# New_Multirotor_CPU_imu_V1_3.net
KiCad netlist of a schematic drawn in EAGLE
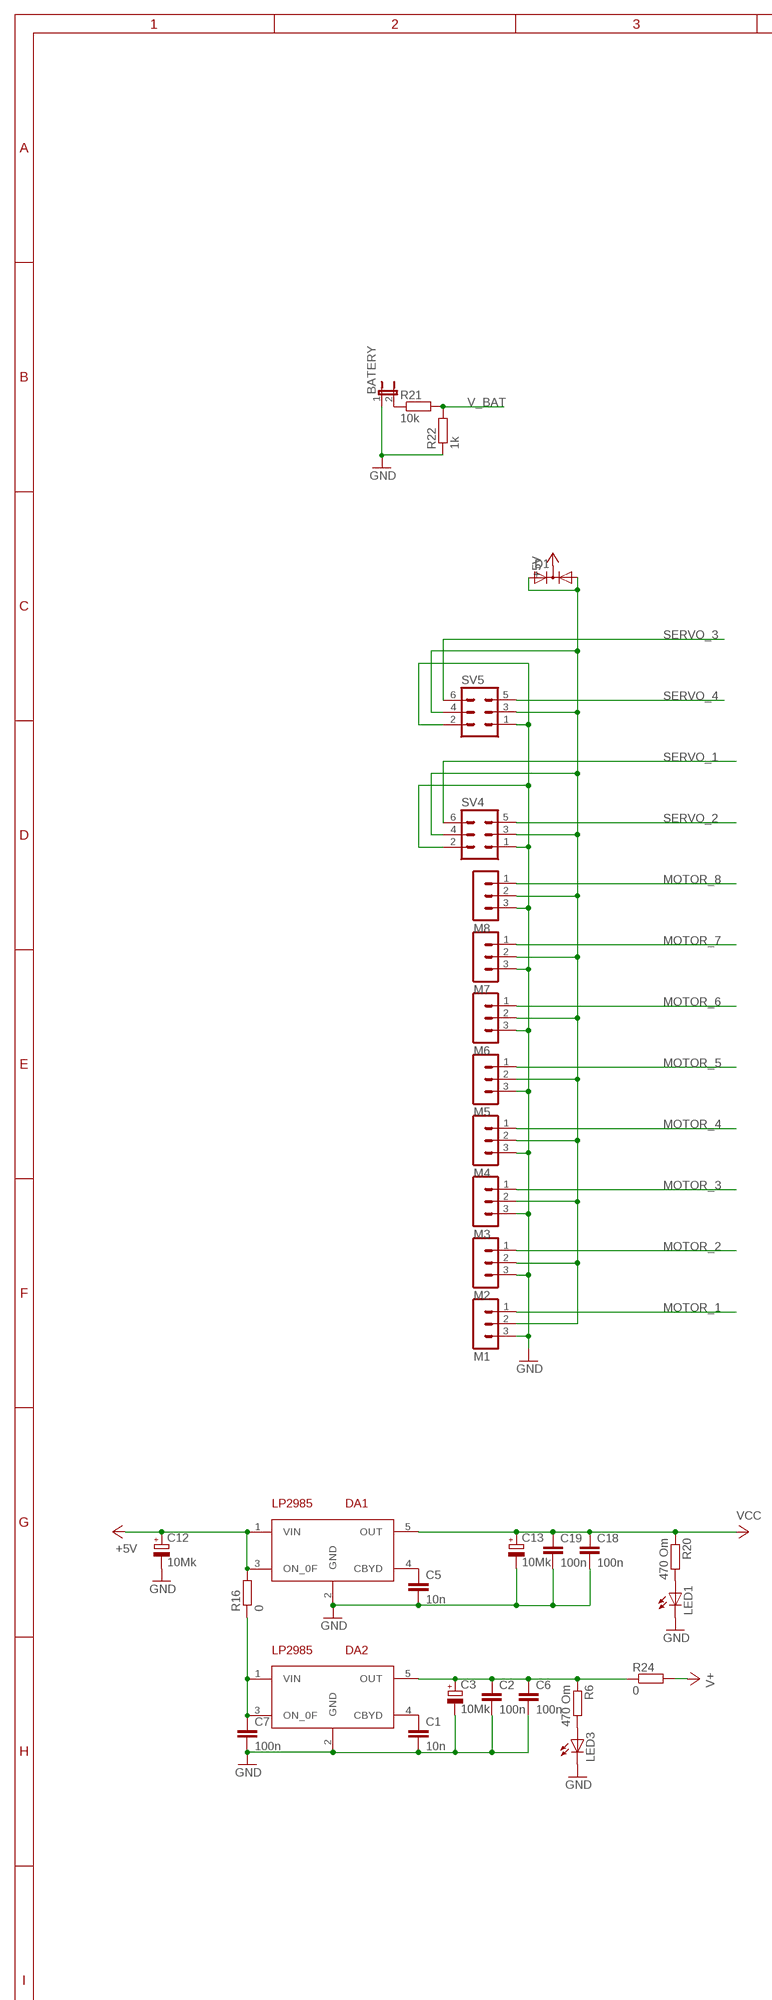
[diagram p0: schematic, sheet 1, part 1 of 2]
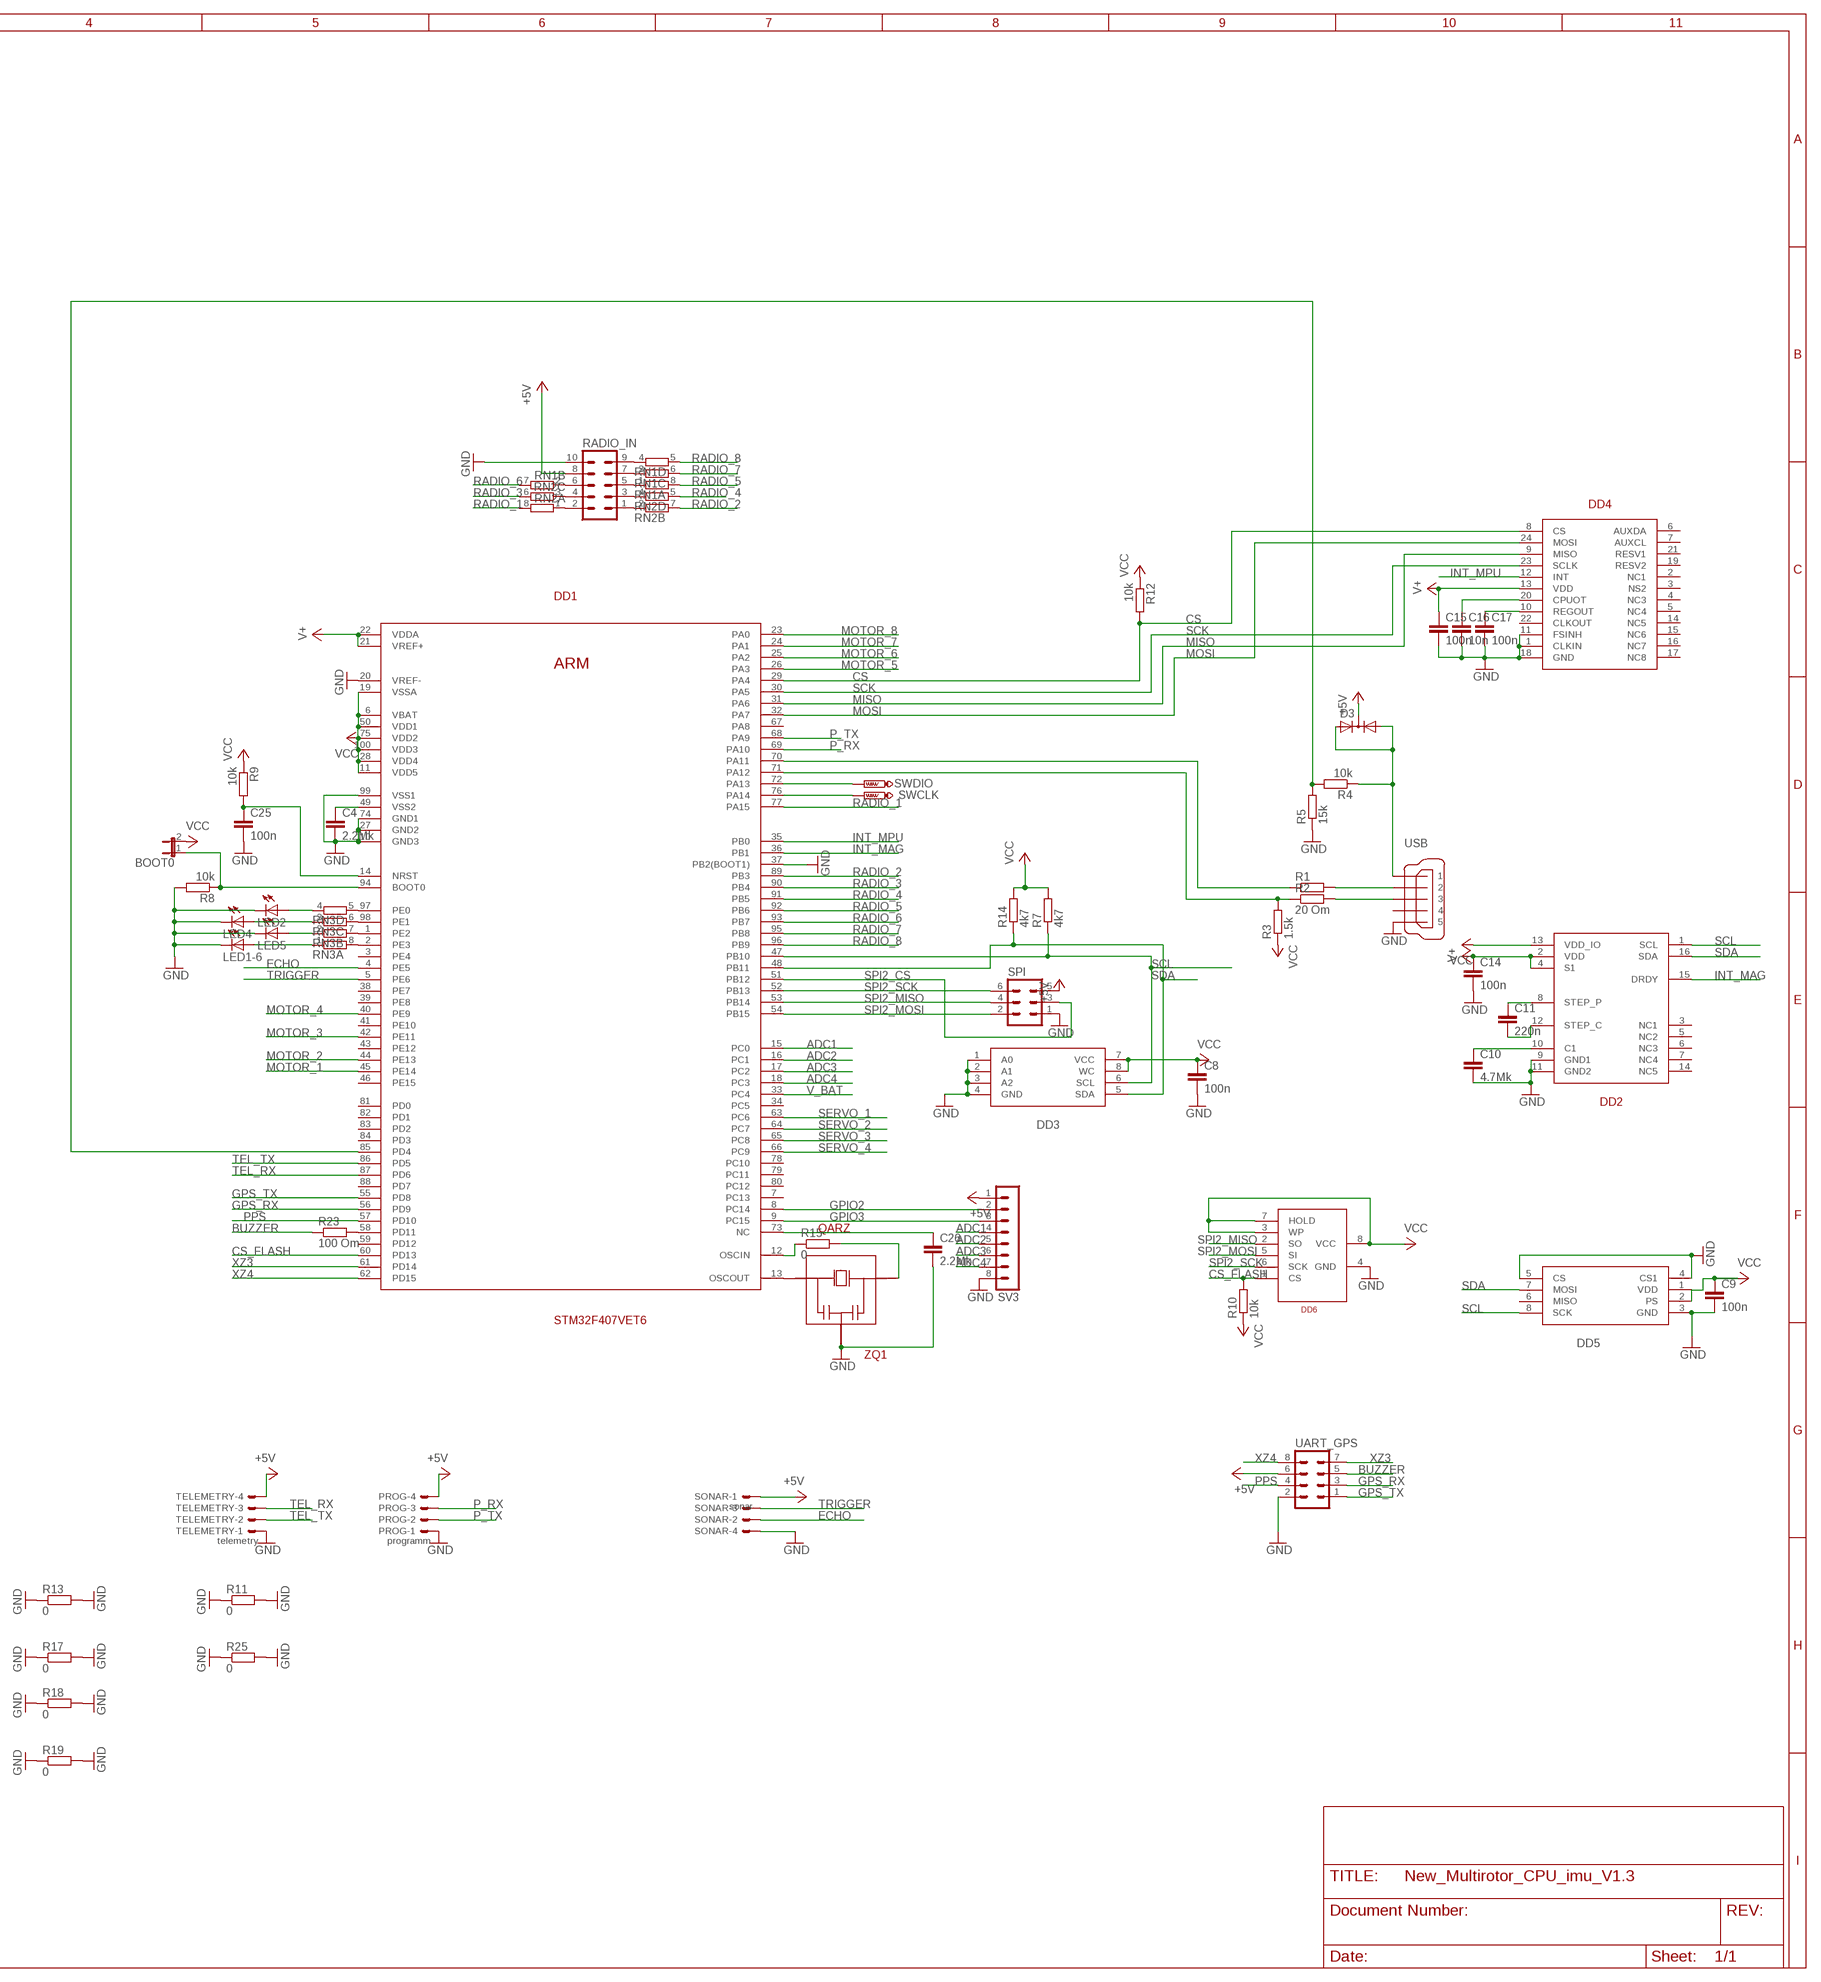
[diagram p1: schematic, sheet 1, part 2 of 2]

(export (version "E")
  (design (tool "Eeschema 10.0.6"))
  (components
    (comp (ref "BATERY")
      (value "JP1E")
      (footprint "eagle-import:JP1")
      (libsource (lib "eagle-import") (part "JP1E"))
    )
    (comp (ref "BOOT0")
      (value "JP1E")
      (footprint "eagle-import:JP1")
      (libsource (lib "eagle-import") (part "JP1E"))
    )
    (comp (ref "C1")
      (value "10n")
      (footprint "eagle-import:C0603K")
      (libsource (lib "eagle-import") (part "C-EUC0603K"))
    )
    (comp (ref "C2")
      (value "100n")
      (footprint "eagle-import:C0603K")
      (libsource (lib "eagle-import") (part "C-EUC0603K"))
    )
    (comp (ref "C3")
      (value "10Mk")
      (footprint "eagle-import:A_3216-18W")
      (libsource (lib "eagle-import") (part "CPOL-EUA/3216-18W"))
    )
    (comp (ref "C4")
      (value "2.2Mk")
      (footprint "eagle-import:C0603K")
      (libsource (lib "eagle-import") (part "C-EUC0603K"))
    )
    (comp (ref "C5")
      (value "10n")
      (footprint "eagle-import:C0603K")
      (libsource (lib "eagle-import") (part "C-EUC0603K"))
    )
    (comp (ref "C6")
      (value "100n")
      (footprint "eagle-import:C0603K")
      (libsource (lib "eagle-import") (part "C-EUC0603K"))
    )
    (comp (ref "C7")
      (value "100n")
      (footprint "eagle-import:C0603K")
      (libsource (lib "eagle-import") (part "C-EUC0603K"))
    )
    (comp (ref "C8")
      (value "100n")
      (footprint "eagle-import:C0603K")
      (libsource (lib "eagle-import") (part "C-EUC0603K"))
    )
    (comp (ref "C9")
      (value "100n")
      (footprint "eagle-import:C0603K")
      (libsource (lib "eagle-import") (part "C-EUC0603K"))
    )
    (comp (ref "C10")
      (value "4.7Mk")
      (footprint "eagle-import:C0603K")
      (libsource (lib "eagle-import") (part "C-EUC0603K"))
    )
    (comp (ref "C11")
      (value "220n")
      (footprint "eagle-import:C0603K")
      (libsource (lib "eagle-import") (part "C-EUC0603K"))
    )
    (comp (ref "C12")
      (value "10Mk")
      (footprint "eagle-import:A_3216-18W")
      (libsource (lib "eagle-import") (part "CPOL-EUA/3216-18W"))
    )
    (comp (ref "C13")
      (value "10Mk")
      (footprint "eagle-import:A_3216-18W")
      (libsource (lib "eagle-import") (part "CPOL-EUA/3216-18W"))
    )
    (comp (ref "C14")
      (value "100n")
      (footprint "eagle-import:C0603K")
      (libsource (lib "eagle-import") (part "C-EUC0603K"))
    )
    (comp (ref "C15")
      (value "100n")
      (footprint "eagle-import:C0603K")
      (libsource (lib "eagle-import") (part "C-EUC0603K"))
    )
    (comp (ref "C16")
      (value "10n")
      (footprint "eagle-import:C0603K")
      (libsource (lib "eagle-import") (part "C-EUC0603K"))
    )
    (comp (ref "C17")
      (value "100n")
      (footprint "eagle-import:C0603K")
      (libsource (lib "eagle-import") (part "C-EUC0603K"))
    )
    (comp (ref "C18")
      (value "100n")
      (footprint "eagle-import:C0603K")
      (libsource (lib "eagle-import") (part "C-EUC0603K"))
    )
    (comp (ref "C19")
      (value "100n")
      (footprint "eagle-import:C0603K")
      (libsource (lib "eagle-import") (part "C-EUC0603K"))
    )
    (comp (ref "C25")
      (value "100n")
      (footprint "eagle-import:C0603K")
      (libsource (lib "eagle-import") (part "C-EUC0603K"))
    )
    (comp (ref "C26")
      (value "2.2Mk")
      (footprint "eagle-import:C0603K")
      (libsource (lib "eagle-import") (part "C-EUC0603K"))
    )
    (comp (ref "D1")
      (value "DIODE-2AC|CASOT23")
      (footprint "eagle-import:SOT23")
      (libsource (lib "eagle-import") (part "DIODE-2AC|CASOT23"))
    )
    (comp (ref "D3")
      (value "DIODE-2AC|CASOT23")
      (footprint "eagle-import:SOT23")
      (libsource (lib "eagle-import") (part "DIODE-2AC|CASOT23"))
    )
    (comp (ref "DA1")
      (value "LP2985")
      (footprint "eagle-import:SOT23-5L")
      (libsource (lib "eagle-import") (part "3.3"))
    )
    (comp (ref "DA2")
      (value "LP2985")
      (footprint "eagle-import:SOT23-5L")
      (libsource (lib "eagle-import") (part "3.3"))
    )
    (comp (ref "DD1")
      (value "STM32F407VET6")
      (footprint "eagle-import:LQFP100")
      (libsource (lib "eagle-import") (part "STM32F407VET6"))
    )
    (comp (ref "DD2")
      (value "HMC5883L")
      (footprint "eagle-import:LCC-16")
      (libsource (lib "eagle-import") (part "HMC5883L"))
    )
    (comp (ref "DD3")
      (value "24C512")
      (footprint "eagle-import:SOIC8")
      (libsource (lib "eagle-import") (part "24C512"))
    )
    (comp (ref "DD4")
      (value "MPU6000")
      (footprint "eagle-import:JEDEC")
      (libsource (lib "eagle-import") (part "MPU6000"))
    )
    (comp (ref "DD5")
      (value "MS5611-01BA03")
      (footprint "eagle-import:MS5611-01BA03")
      (libsource (lib "eagle-import") (part "MS5611-01BA03"))
    )
    (comp (ref "DD6")
      (value "W25X40")
      (footprint "eagle-import:SOIC8")
      (libsource (lib "eagle-import") (part "W25X40"))
    )
    (comp (ref "LED1")
      (value "LEDCHIPLED_0603")
      (footprint "eagle-import:CHIPLED_0603")
      (libsource (lib "eagle-import") (part "LEDCHIPLED_0603"))
    )
    (comp (ref "LED1-6")
      (value "LEDCHIPLED_0603")
      (footprint "eagle-import:CHIPLED_0603")
      (libsource (lib "eagle-import") (part "LEDCHIPLED_0603"))
    )
    (comp (ref "LED2")
      (value "LEDCHIPLED_0603")
      (footprint "eagle-import:CHIPLED_0603")
      (libsource (lib "eagle-import") (part "LEDCHIPLED_0603"))
    )
    (comp (ref "LED3")
      (value "LEDCHIPLED_0603")
      (footprint "eagle-import:CHIPLED_0603")
      (libsource (lib "eagle-import") (part "LEDCHIPLED_0603"))
    )
    (comp (ref "LED4")
      (value "LEDCHIPLED_0603")
      (footprint "eagle-import:CHIPLED_0603")
      (libsource (lib "eagle-import") (part "LEDCHIPLED_0603"))
    )
    (comp (ref "LED5")
      (value "LEDCHIPLED_0603")
      (footprint "eagle-import:CHIPLED_0603")
      (libsource (lib "eagle-import") (part "LEDCHIPLED_0603"))
    )
    (comp (ref "M1")
      (value "MA03-1")
      (footprint "eagle-import:MA03-1")
      (fields (field (name "OC_FARNELL") "unknown") (field (name "OC_NEWARK") "unknown"))
      (libsource (lib "eagle-import") (part "MA03-1"))
    )
    (comp (ref "M2")
      (value "MA03-1")
      (footprint "eagle-import:MA03-1")
      (fields (field (name "OC_FARNELL") "unknown") (field (name "OC_NEWARK") "unknown"))
      (libsource (lib "eagle-import") (part "MA03-1"))
    )
    (comp (ref "M3")
      (value "MA03-1")
      (footprint "eagle-import:MA03-1")
      (fields (field (name "OC_FARNELL") "unknown") (field (name "OC_NEWARK") "unknown"))
      (libsource (lib "eagle-import") (part "MA03-1"))
    )
    (comp (ref "M4")
      (value "MA03-1")
      (footprint "eagle-import:MA03-1")
      (fields (field (name "OC_FARNELL") "unknown") (field (name "OC_NEWARK") "unknown"))
      (libsource (lib "eagle-import") (part "MA03-1"))
    )
    (comp (ref "M5")
      (value "MA03-1")
      (footprint "eagle-import:MA03-1")
      (fields (field (name "OC_FARNELL") "unknown") (field (name "OC_NEWARK") "unknown"))
      (libsource (lib "eagle-import") (part "MA03-1"))
    )
    (comp (ref "M6")
      (value "MA03-1")
      (footprint "eagle-import:MA03-1")
      (fields (field (name "OC_FARNELL") "unknown") (field (name "OC_NEWARK") "unknown"))
      (libsource (lib "eagle-import") (part "MA03-1"))
    )
    (comp (ref "M7")
      (value "MA03-1")
      (footprint "eagle-import:MA03-1")
      (fields (field (name "OC_FARNELL") "unknown") (field (name "OC_NEWARK") "unknown"))
      (libsource (lib "eagle-import") (part "MA03-1"))
    )
    (comp (ref "M8")
      (value "MA03-1")
      (footprint "eagle-import:MA03-1")
      (fields (field (name "OC_FARNELL") "unknown") (field (name "OC_NEWARK") "unknown"))
      (libsource (lib "eagle-import") (part "MA03-1"))
    )
    (comp (ref "PROG")
      (value "programm")
      (footprint "eagle-import:SM04B-SRSS-TB")
      (libsource (lib "eagle-import") (part "?M04B-SRSS-TBS"))
    )
    (comp (ref "R1")
      (value "R-EU_R0603")
      (footprint "eagle-import:R0603")
      (libsource (lib "eagle-import") (part "R-EU_R0603"))
    )
    (comp (ref "R2")
      (value "20 Om")
      (footprint "eagle-import:R0603")
      (libsource (lib "eagle-import") (part "R-EU_R0603"))
    )
    (comp (ref "R3")
      (value "1.5k")
      (footprint "eagle-import:R0603")
      (libsource (lib "eagle-import") (part "R-EU_R0603"))
    )
    (comp (ref "R4")
      (value "10k")
      (footprint "eagle-import:R0603")
      (libsource (lib "eagle-import") (part "R-EU_R0603"))
    )
    (comp (ref "R5")
      (value "15k")
      (footprint "eagle-import:R0603")
      (libsource (lib "eagle-import") (part "R-EU_R0603"))
    )
    (comp (ref "R6")
      (value "470 Om")
      (footprint "eagle-import:R0603")
      (libsource (lib "eagle-import") (part "R-EU_R0603"))
    )
    (comp (ref "R7")
      (value "4k7")
      (footprint "eagle-import:R0603")
      (libsource (lib "eagle-import") (part "R-EU_R0603"))
    )
    (comp (ref "R8")
      (value "10k")
      (footprint "eagle-import:R0603")
      (libsource (lib "eagle-import") (part "R-EU_R0603"))
    )
    (comp (ref "R9")
      (value "10k")
      (footprint "eagle-import:R0603")
      (libsource (lib "eagle-import") (part "R-EU_R0603"))
    )
    (comp (ref "R10")
      (value "10k")
      (footprint "eagle-import:R0603")
      (libsource (lib "eagle-import") (part "R-EU_R0603"))
    )
    (comp (ref "R11")
      (value "0")
      (footprint "eagle-import:R0603")
      (libsource (lib "eagle-import") (part "R-EU_R0603"))
    )
    (comp (ref "R12")
      (value "10k")
      (footprint "eagle-import:R0603")
      (libsource (lib "eagle-import") (part "R-EU_R0603"))
    )
    (comp (ref "R13")
      (value "0")
      (footprint "eagle-import:R0603")
      (libsource (lib "eagle-import") (part "R-EU_R0603"))
    )
    (comp (ref "R14")
      (value "4k7")
      (footprint "eagle-import:R0603")
      (libsource (lib "eagle-import") (part "R-EU_R0603"))
    )
    (comp (ref "R15")
      (value "0")
      (footprint "eagle-import:R0603")
      (libsource (lib "eagle-import") (part "R-EU_R0603"))
    )
    (comp (ref "R16")
      (value "0")
      (footprint "eagle-import:R0603")
      (libsource (lib "eagle-import") (part "R-EU_R0603"))
    )
    (comp (ref "R17")
      (value "0")
      (footprint "eagle-import:R0603")
      (libsource (lib "eagle-import") (part "R-EU_R0603"))
    )
    (comp (ref "R18")
      (value "0")
      (footprint "eagle-import:R0603")
      (libsource (lib "eagle-import") (part "R-EU_R0603"))
    )
    (comp (ref "R19")
      (value "0")
      (footprint "eagle-import:R0603")
      (libsource (lib "eagle-import") (part "R-EU_R0603"))
    )
    (comp (ref "R20")
      (value "470 Om")
      (footprint "eagle-import:R0603")
      (libsource (lib "eagle-import") (part "R-EU_R0603"))
    )
    (comp (ref "R21")
      (value "10k")
      (footprint "eagle-import:R0603")
      (libsource (lib "eagle-import") (part "R-EU_R0603"))
    )
    (comp (ref "R22")
      (value "1k")
      (footprint "eagle-import:R0603")
      (libsource (lib "eagle-import") (part "R-EU_R0603"))
    )
    (comp (ref "R23")
      (value "100 Om")
      (footprint "eagle-import:R0603")
      (libsource (lib "eagle-import") (part "R-EU_R0603"))
    )
    (comp (ref "R24")
      (value "0")
      (footprint "eagle-import:R0603")
      (libsource (lib "eagle-import") (part "R-EU_R0603"))
    )
    (comp (ref "R25")
      (value "0")
      (footprint "eagle-import:R0603")
      (libsource (lib "eagle-import") (part "R-EU_R0603"))
    )
    (comp (ref "RADIO_IN")
      (value "MA05-2")
      (footprint "eagle-import:MA05-2")
      (libsource (lib "eagle-import") (part "MA05-2"))
    )
    (comp (ref "RN1")
      (value "4R-N0603-ARV")
      (footprint "eagle-import:0603-ARV")
      (libsource (lib "eagle-import") (part "4R-N0603-ARV"))
    )
    (comp (ref "RN2")
      (value "4R-N0603-ARV")
      (footprint "eagle-import:0603-ARV")
      (libsource (lib "eagle-import") (part "4R-N0603-ARV"))
    )
    (comp (ref "RN3")
      (value "4R-N0603-ARV")
      (footprint "eagle-import:0603-ARV")
      (libsource (lib "eagle-import") (part "4R-N0603-ARV"))
    )
    (comp (ref "SONAR")
      (value "sonar")
      (footprint "eagle-import:SM04B-SRSS-TB")
      (libsource (lib "eagle-import") (part "?M04B-SRSS-TBS"))
    )
    (comp (ref "SPI")
      (value "MA03-2")
      (footprint "eagle-import:MA03-2")
      (libsource (lib "eagle-import") (part "MA03-2"))
    )
    (comp (ref "SV3")
      (value "MA08-1")
      (footprint "eagle-import:MA08-1")
      (libsource (lib "eagle-import") (part "MA08-1"))
    )
    (comp (ref "SV4")
      (value "MA03-2")
      (footprint "eagle-import:MA03-2")
      (libsource (lib "eagle-import") (part "MA03-2"))
    )
    (comp (ref "SV5")
      (value "MA03-2")
      (footprint "eagle-import:MA03-2")
      (libsource (lib "eagle-import") (part "MA03-2"))
    )
    (comp (ref "SWCLK")
      (value "PTR1TP12R")
      (footprint "eagle-import:TP12R")
      (libsource (lib "eagle-import") (part "PTR1TP12R"))
    )
    (comp (ref "SWDIO")
      (value "PTR1TP12R")
      (footprint "eagle-import:TP12R")
      (libsource (lib "eagle-import") (part "PTR1TP12R"))
    )
    (comp (ref "TELEMETRY")
      (value "telemetry")
      (footprint "eagle-import:SM04B-SRSS-TB")
      (libsource (lib "eagle-import") (part "?M04B-SRSS-TBS"))
    )
    (comp (ref "UART_GPS")
      (value "MA04-2")
      (footprint "eagle-import:MA04-2")
      (libsource (lib "eagle-import") (part "MA04-2"))
    )
    (comp (ref "USB")
      (value "MINI-USB-32005-201")
      (footprint "eagle-import:32005-201")
      (libsource (lib "eagle-import") (part "MINI-USB-32005-201"))
    )
    (comp (ref "ZQ1")
      (value "QARZ")
      (footprint "eagle-import:QARZ")
      (libsource (lib "eagle-import") (part "QARZ"))
    )
  )
  (nets
    (net (code "1") (name "+5V") (class "Default")
      (node (ref "C12") (pin "+") (pinfunction "+_+") (pintype "passive"))
      (node (ref "D1") (pin "3") (pinfunction "C_3") (pintype "passive"))
      (node (ref "D3") (pin "3") (pinfunction "C_3") (pintype "passive"))
      (node (ref "DA1") (pin "1") (pinfunction "VIN_1") (pintype "bidirectional"))
      (node (ref "DA1") (pin "3") (pinfunction "ON_0F_3") (pintype "bidirectional"))
      (node (ref "PROG") (pin "4") (pinfunction "S_4") (pintype "passive"))
      (node (ref "R16") (pin "2") (pinfunction "2_2") (pintype "passive"))
      (node (ref "RADIO_IN") (pin "8") (pinfunction "8_8") (pintype "passive"))
      (node (ref "SONAR") (pin "1") (pinfunction "S_1") (pintype "passive"))
      (node (ref "SPI") (pin "5") (pinfunction "5_5") (pintype "passive"))
      (node (ref "SV3") (pin "1") (pinfunction "1_1") (pintype "passive"))
      (node (ref "TELEMETRY") (pin "4") (pinfunction "S_4") (pintype "passive"))
      (node (ref "UART_GPS") (pin "6") (pinfunction "6_6") (pintype "passive"))
    )
    (net (code "2") (name "/ADC1") (class "Default")
      (node (ref "DD1") (pin "15") (pinfunction "PC0_15") (pintype "bidirectional"))
      (node (ref "SV3") (pin "4") (pinfunction "4_4") (pintype "passive"))
    )
    (net (code "3") (name "/ADC2") (class "Default")
      (node (ref "DD1") (pin "16") (pinfunction "PC1_16") (pintype "bidirectional"))
      (node (ref "SV3") (pin "5") (pinfunction "5_5") (pintype "passive"))
    )
    (net (code "4") (name "/ADC3") (class "Default")
      (node (ref "DD1") (pin "17") (pinfunction "PC2_17") (pintype "bidirectional"))
      (node (ref "SV3") (pin "6") (pinfunction "6_6") (pintype "passive"))
    )
    (net (code "5") (name "/ADC4") (class "Default")
      (node (ref "DD1") (pin "18") (pinfunction "PC3_18") (pintype "bidirectional"))
      (node (ref "SV3") (pin "7") (pinfunction "7_7") (pintype "passive"))
    )
    (net (code "6") (name "/BUZZER") (class "Default")
      (node (ref "R23") (pin "1") (pinfunction "1_1") (pintype "passive"))
      (node (ref "UART_GPS") (pin "5") (pinfunction "5_5") (pintype "passive"))
    )
    (net (code "7") (name "/CS") (class "Default")
      (node (ref "DD1") (pin "29") (pinfunction "PA4_29") (pintype "bidirectional"))
      (node (ref "DD4") (pin "8") (pinfunction "CS_8") (pintype "bidirectional"))
      (node (ref "R12") (pin "2") (pinfunction "2_2") (pintype "passive"))
    )
    (net (code "8") (name "/CS_FLASH") (class "Default")
      (node (ref "DD1") (pin "60") (pinfunction "PD13_60") (pintype "bidirectional"))
      (node (ref "DD6") (pin "1") (pinfunction "CS_1") (pintype "bidirectional"))
      (node (ref "R10") (pin "2") (pinfunction "2_2") (pintype "passive"))
    )
    (net (code "9") (name "/ECHO") (class "Default")
      (node (ref "DD1") (pin "4") (pinfunction "PE5_4") (pintype "bidirectional"))
      (node (ref "SONAR") (pin "2") (pinfunction "S_2") (pintype "passive"))
    )
    (net (code "10") (name "/GPIO2") (class "Default")
      (node (ref "DD1") (pin "8") (pinfunction "PC14_8") (pintype "bidirectional"))
      (node (ref "SV3") (pin "2") (pinfunction "2_2") (pintype "passive"))
    )
    (net (code "11") (name "/GPIO3") (class "Default")
      (node (ref "DD1") (pin "9") (pinfunction "PC15_9") (pintype "bidirectional"))
      (node (ref "SV3") (pin "3") (pinfunction "3_3") (pintype "passive"))
    )
    (net (code "12") (name "/GPS_RX") (class "Default")
      (node (ref "DD1") (pin "56") (pinfunction "PD9_56") (pintype "bidirectional"))
      (node (ref "UART_GPS") (pin "3") (pinfunction "3_3") (pintype "passive"))
    )
    (net (code "13") (name "/GPS_TX") (class "Default")
      (node (ref "DD1") (pin "55") (pinfunction "PD8_55") (pintype "bidirectional"))
      (node (ref "UART_GPS") (pin "1") (pinfunction "1_1") (pintype "passive"))
    )
    (net (code "14") (name "/INT_MAG") (class "Default")
      (node (ref "DD1") (pin "36") (pinfunction "PB1_36") (pintype "bidirectional"))
      (node (ref "DD2") (pin "15") (pinfunction "DRDY_15") (pintype "bidirectional"))
    )
    (net (code "15") (name "/INT_MPU") (class "Default")
      (node (ref "DD1") (pin "35") (pinfunction "PB0_35") (pintype "bidirectional"))
      (node (ref "DD4") (pin "12") (pinfunction "INT_12") (pintype "bidirectional"))
    )
    (net (code "16") (name "/MISO") (class "Default")
      (node (ref "DD1") (pin "31") (pinfunction "PA6_31") (pintype "bidirectional"))
      (node (ref "DD4") (pin "9") (pinfunction "MISO_9") (pintype "bidirectional"))
    )
    (net (code "17") (name "/MOSI") (class "Default")
      (node (ref "DD1") (pin "32") (pinfunction "PA7_32") (pintype "bidirectional"))
      (node (ref "DD4") (pin "24") (pinfunction "MOSI_24") (pintype "bidirectional"))
    )
    (net (code "18") (name "/MOTOR_1") (class "Default")
      (node (ref "DD1") (pin "45") (pinfunction "PE14_45") (pintype "bidirectional"))
      (node (ref "M1") (pin "1") (pinfunction "1_1") (pintype "passive"))
    )
    (net (code "19") (name "/MOTOR_2") (class "Default")
      (node (ref "DD1") (pin "44") (pinfunction "PE13_44") (pintype "bidirectional"))
      (node (ref "M2") (pin "1") (pinfunction "1_1") (pintype "passive"))
    )
    (net (code "20") (name "/MOTOR_3") (class "Default")
      (node (ref "DD1") (pin "42") (pinfunction "PE11_42") (pintype "bidirectional"))
      (node (ref "M3") (pin "1") (pinfunction "1_1") (pintype "passive"))
    )
    (net (code "21") (name "/MOTOR_4") (class "Default")
      (node (ref "DD1") (pin "40") (pinfunction "PE9_40") (pintype "bidirectional"))
      (node (ref "M4") (pin "1") (pinfunction "1_1") (pintype "passive"))
    )
    (net (code "22") (name "/MOTOR_5") (class "Default")
      (node (ref "DD1") (pin "26") (pinfunction "PA3_26") (pintype "bidirectional"))
      (node (ref "M5") (pin "1") (pinfunction "1_1") (pintype "passive"))
    )
    (net (code "23") (name "/MOTOR_6") (class "Default")
      (node (ref "DD1") (pin "25") (pinfunction "PA2_25") (pintype "bidirectional"))
      (node (ref "M6") (pin "1") (pinfunction "1_1") (pintype "passive"))
    )
    (net (code "24") (name "/MOTOR_7") (class "Default")
      (node (ref "DD1") (pin "24") (pinfunction "PA1_24") (pintype "bidirectional"))
      (node (ref "M7") (pin "1") (pinfunction "1_1") (pintype "passive"))
    )
    (net (code "25") (name "/MOTOR_8") (class "Default")
      (node (ref "DD1") (pin "23") (pinfunction "PA0_23") (pintype "bidirectional"))
      (node (ref "M8") (pin "1") (pinfunction "1_1") (pintype "passive"))
    )
    (net (code "26") (name "/PPS") (class "Default")
      (node (ref "DD1") (pin "57") (pinfunction "PD10_57") (pintype "bidirectional"))
      (node (ref "UART_GPS") (pin "4") (pinfunction "4_4") (pintype "passive"))
    )
    (net (code "27") (name "/P_RX") (class "Default")
      (node (ref "DD1") (pin "69") (pinfunction "PA10_69") (pintype "bidirectional"))
      (node (ref "PROG") (pin "3") (pinfunction "S_3") (pintype "passive"))
    )
    (net (code "28") (name "/P_TX") (class "Default")
      (node (ref "DD1") (pin "68") (pinfunction "PA9_68") (pintype "bidirectional"))
      (node (ref "PROG") (pin "2") (pinfunction "S_2") (pintype "passive"))
    )
    (net (code "29") (name "/RADIO_1") (class "Default")
      (node (ref "DD1") (pin "77") (pinfunction "PA15_77") (pintype "bidirectional"))
      (node (ref "RN2") (pin "8") (pinfunction "2_8") (pintype "passive"))
    )
    (net (code "30") (name "/RADIO_2") (class "Default")
      (node (ref "DD1") (pin "89") (pinfunction "PB3_89") (pintype "bidirectional"))
      (node (ref "RN2") (pin "7") (pinfunction "2_7") (pintype "passive"))
    )
    (net (code "31") (name "/RADIO_3") (class "Default")
      (node (ref "DD1") (pin "90") (pinfunction "PB4_90") (pintype "bidirectional"))
      (node (ref "RN2") (pin "6") (pinfunction "2_6") (pintype "passive"))
    )
    (net (code "32") (name "/RADIO_4") (class "Default")
      (node (ref "DD1") (pin "91") (pinfunction "PB5_91") (pintype "bidirectional"))
      (node (ref "RN2") (pin "5") (pinfunction "2_5") (pintype "passive"))
    )
    (net (code "33") (name "/RADIO_5") (class "Default")
      (node (ref "DD1") (pin "92") (pinfunction "PB6_92") (pintype "bidirectional"))
      (node (ref "RN1") (pin "8") (pinfunction "2_8") (pintype "passive"))
    )
    (net (code "34") (name "/RADIO_6") (class "Default")
      (node (ref "DD1") (pin "93") (pinfunction "PB7_93") (pintype "bidirectional"))
      (node (ref "RN1") (pin "7") (pinfunction "2_7") (pintype "passive"))
    )
    (net (code "35") (name "/RADIO_7") (class "Default")
      (node (ref "DD1") (pin "95") (pinfunction "PB8_95") (pintype "bidirectional"))
      (node (ref "RN1") (pin "6") (pinfunction "2_6") (pintype "passive"))
    )
    (net (code "36") (name "/RADIO_8") (class "Default")
      (node (ref "DD1") (pin "96") (pinfunction "PB9_96") (pintype "bidirectional"))
      (node (ref "RN1") (pin "5") (pinfunction "2_5") (pintype "passive"))
    )
    (net (code "37") (name "/SCK") (class "Default")
      (node (ref "DD1") (pin "30") (pinfunction "PA5_30") (pintype "bidirectional"))
      (node (ref "DD4") (pin "23") (pinfunction "SCLK_23") (pintype "bidirectional"))
    )
    (net (code "38") (name "/SCL") (class "Default")
      (node (ref "DD1") (pin "47") (pinfunction "PB10_47") (pintype "bidirectional"))
      (node (ref "DD2") (pin "1") (pinfunction "SCL_1") (pintype "bidirectional"))
      (node (ref "DD3") (pin "6") (pinfunction "SCL_6") (pintype "bidirectional"))
      (node (ref "DD5") (pin "8") (pinfunction "SCK_8") (pintype "bidirectional"))
      (node (ref "R7") (pin "1") (pinfunction "1_1") (pintype "passive"))
    )
    (net (code "39") (name "/SDA") (class "Default")
      (node (ref "DD1") (pin "48") (pinfunction "PB11_48") (pintype "bidirectional"))
      (node (ref "DD2") (pin "16") (pinfunction "SDA_16") (pintype "bidirectional"))
      (node (ref "DD3") (pin "5") (pinfunction "SDA_5") (pintype "bidirectional"))
      (node (ref "DD5") (pin "7") (pinfunction "MOSI_7") (pintype "bidirectional"))
      (node (ref "R14") (pin "1") (pinfunction "1_1") (pintype "passive"))
    )
    (net (code "40") (name "/SERVO_1") (class "Default")
      (node (ref "DD1") (pin "63") (pinfunction "PC6_63") (pintype "bidirectional"))
      (node (ref "SV4") (pin "6") (pinfunction "6_6") (pintype "passive"))
    )
    (net (code "41") (name "/SERVO_2") (class "Default")
      (node (ref "DD1") (pin "64") (pinfunction "PC7_64") (pintype "bidirectional"))
      (node (ref "SV4") (pin "5") (pinfunction "5_5") (pintype "passive"))
    )
    (net (code "42") (name "/SERVO_3") (class "Default")
      (node (ref "DD1") (pin "65") (pinfunction "PC8_65") (pintype "bidirectional"))
      (node (ref "SV5") (pin "6") (pinfunction "6_6") (pintype "passive"))
    )
    (net (code "43") (name "/SERVO_4") (class "Default")
      (node (ref "DD1") (pin "66") (pinfunction "PC9_66") (pintype "bidirectional"))
      (node (ref "SV5") (pin "5") (pinfunction "5_5") (pintype "passive"))
    )
    (net (code "44") (name "/SPI2_CS") (class "Default")
      (node (ref "DD1") (pin "51") (pinfunction "PB12_51") (pintype "bidirectional"))
      (node (ref "SPI") (pin "3") (pinfunction "3_3") (pintype "passive"))
    )
    (net (code "45") (name "/SPI2_MISO") (class "Default")
      (node (ref "DD1") (pin "53") (pinfunction "PB14_53") (pintype "bidirectional"))
      (node (ref "DD6") (pin "2") (pinfunction "SO_2") (pintype "bidirectional"))
      (node (ref "SPI") (pin "4") (pinfunction "4_4") (pintype "passive"))
    )
    (net (code "46") (name "/SPI2_MOSI") (class "Default")
      (node (ref "DD1") (pin "54") (pinfunction "PB15_54") (pintype "bidirectional"))
      (node (ref "DD6") (pin "5") (pinfunction "SI_5") (pintype "bidirectional"))
      (node (ref "SPI") (pin "2") (pinfunction "2_2") (pintype "passive"))
    )
    (net (code "47") (name "/SPI2_SCK") (class "Default")
      (node (ref "DD1") (pin "52") (pinfunction "PB13_52") (pintype "bidirectional"))
      (node (ref "DD6") (pin "6") (pinfunction "SCK_6") (pintype "bidirectional"))
      (node (ref "SPI") (pin "6") (pinfunction "6_6") (pintype "passive"))
    )
    (net (code "48") (name "/TEL_RX") (class "Default")
      (node (ref "DD1") (pin "87") (pinfunction "PD6_87") (pintype "bidirectional"))
      (node (ref "TELEMETRY") (pin "3") (pinfunction "S_3") (pintype "passive"))
    )
    (net (code "49") (name "/TEL_TX") (class "Default")
      (node (ref "DD1") (pin "86") (pinfunction "PD5_86") (pintype "bidirectional"))
      (node (ref "TELEMETRY") (pin "2") (pinfunction "S_2") (pintype "passive"))
    )
    (net (code "50") (name "/TRIGGER") (class "Default")
      (node (ref "DD1") (pin "5") (pinfunction "PE6_5") (pintype "bidirectional"))
      (node (ref "SONAR") (pin "3") (pinfunction "S_3") (pintype "passive"))
    )
    (net (code "51") (name "/V_BAT") (class "Default")
      (node (ref "DD1") (pin "33") (pinfunction "PC4_33") (pintype "bidirectional"))
      (node (ref "R21") (pin "2") (pinfunction "2_2") (pintype "passive"))
      (node (ref "R22") (pin "2") (pinfunction "2_2") (pintype "passive"))
    )
    (net (code "52") (name "/XZ3") (class "Default")
      (node (ref "DD1") (pin "61") (pinfunction "PD14_61") (pintype "bidirectional"))
      (node (ref "UART_GPS") (pin "7") (pinfunction "7_7") (pintype "passive"))
    )
    (net (code "53") (name "/XZ4") (class "Default")
      (node (ref "DD1") (pin "62") (pinfunction "PD15_62") (pintype "bidirectional"))
      (node (ref "UART_GPS") (pin "8") (pinfunction "8_8") (pintype "passive"))
    )
    (net (code "54") (name "GND") (class "Default")
      (node (ref "BATERY") (pin "1") (pinfunction "1_1") (pintype "passive"))
      (node (ref "C1") (pin "2") (pinfunction "2_2") (pintype "passive"))
      (node (ref "C10") (pin "2") (pinfunction "2_2") (pintype "passive"))
      (node (ref "C12") (pin "-") (pinfunction "-_-") (pintype "passive"))
      (node (ref "C13") (pin "-") (pinfunction "-_-") (pintype "passive"))
      (node (ref "C14") (pin "2") (pinfunction "2_2") (pintype "passive"))
      (node (ref "C15") (pin "2") (pinfunction "2_2") (pintype "passive"))
      (node (ref "C16") (pin "2") (pinfunction "2_2") (pintype "passive"))
      (node (ref "C17") (pin "2") (pinfunction "2_2") (pintype "passive"))
      (node (ref "C18") (pin "2") (pinfunction "2_2") (pintype "passive"))
      (node (ref "C19") (pin "2") (pinfunction "2_2") (pintype "passive"))
      (node (ref "C2") (pin "2") (pinfunction "2_2") (pintype "passive"))
      (node (ref "C25") (pin "2") (pinfunction "2_2") (pintype "passive"))
      (node (ref "C26") (pin "2") (pinfunction "2_2") (pintype "passive"))
      (node (ref "C3") (pin "-") (pinfunction "-_-") (pintype "passive"))
      (node (ref "C4") (pin "2") (pinfunction "2_2") (pintype "passive"))
      (node (ref "C5") (pin "2") (pinfunction "2_2") (pintype "passive"))
      (node (ref "C6") (pin "2") (pinfunction "2_2") (pintype "passive"))
      (node (ref "C7") (pin "2") (pinfunction "2_2") (pintype "passive"))
      (node (ref "C8") (pin "2") (pinfunction "2_2") (pintype "passive"))
      (node (ref "C9") (pin "2") (pinfunction "2_2") (pintype "passive"))
      (node (ref "DA1") (pin "2") (pinfunction "GND_2") (pintype "bidirectional"))
      (node (ref "DA2") (pin "2") (pinfunction "GND_2") (pintype "bidirectional"))
      (node (ref "DD1") (pin "10") (pinfunction "GND3_10") (pintype "bidirectional"))
      (node (ref "DD1") (pin "20") (pinfunction "VREF-_20") (pintype "bidirectional"))
      (node (ref "DD1") (pin "27") (pinfunction "GND2_27") (pintype "bidirectional"))
      (node (ref "DD1") (pin "37") (pinfunction "PB2(BOOT1)_37") (pintype "bidirectional"))
      (node (ref "DD1") (pin "74") (pinfunction "GND1_74") (pintype "bidirectional"))
      (node (ref "DD1") (pin "99") (pinfunction "VSS1_99") (pintype "bidirectional"))
      (node (ref "DD2") (pin "11") (pinfunction "GND2_11") (pintype "bidirectional"))
      (node (ref "DD2") (pin "9") (pinfunction "GND1_9") (pintype "bidirectional"))
      (node (ref "DD3") (pin "1") (pinfunction "A0_1") (pintype "bidirectional"))
      (node (ref "DD3") (pin "2") (pinfunction "A1_2") (pintype "bidirectional"))
      (node (ref "DD3") (pin "3") (pinfunction "A2_3") (pintype "bidirectional"))
      (node (ref "DD3") (pin "4") (pinfunction "GND_4") (pintype "bidirectional"))
      (node (ref "DD4") (pin "1") (pinfunction "CLKIN_1") (pintype "bidirectional"))
      (node (ref "DD4") (pin "11") (pinfunction "FSINH_11") (pintype "bidirectional"))
      (node (ref "DD4") (pin "18") (pinfunction "GND_18") (pintype "bidirectional"))
      (node (ref "DD5") (pin "3") (pinfunction "GND_3") (pintype "bidirectional"))
      (node (ref "DD5") (pin "4") (pinfunction "CS1_4") (pintype "bidirectional"))
      (node (ref "DD5") (pin "5") (pinfunction "CS_5") (pintype "bidirectional"))
      (node (ref "DD6") (pin "4") (pinfunction "GND_4") (pintype "bidirectional"))
      (node (ref "LED1") (pin "C") (pinfunction "C_C") (pintype "passive"))
      (node (ref "LED1-6") (pin "C") (pinfunction "C_C") (pintype "passive"))
      (node (ref "LED2") (pin "C") (pinfunction "C_C") (pintype "passive"))
      (node (ref "LED3") (pin "C") (pinfunction "C_C") (pintype "passive"))
      (node (ref "LED4") (pin "C") (pinfunction "C_C") (pintype "passive"))
      (node (ref "LED5") (pin "C") (pinfunction "C_C") (pintype "passive"))
      (node (ref "M1") (pin "3") (pinfunction "3_3") (pintype "passive"))
      (node (ref "M2") (pin "3") (pinfunction "3_3") (pintype "passive"))
      (node (ref "M3") (pin "3") (pinfunction "3_3") (pintype "passive"))
      (node (ref "M4") (pin "3") (pinfunction "3_3") (pintype "passive"))
      (node (ref "M5") (pin "3") (pinfunction "3_3") (pintype "passive"))
      (node (ref "M6") (pin "3") (pinfunction "3_3") (pintype "passive"))
      (node (ref "M7") (pin "3") (pinfunction "3_3") (pintype "passive"))
      (node (ref "M8") (pin "3") (pinfunction "3_3") (pintype "passive"))
      (node (ref "PROG") (pin "1") (pinfunction "S_1") (pintype "passive"))
      (node (ref "R11") (pin "1") (pinfunction "1_1") (pintype "passive"))
      (node (ref "R11") (pin "2") (pinfunction "2_2") (pintype "passive"))
      (node (ref "R13") (pin "1") (pinfunction "1_1") (pintype "passive"))
      (node (ref "R13") (pin "2") (pinfunction "2_2") (pintype "passive"))
      (node (ref "R17") (pin "1") (pinfunction "1_1") (pintype "passive"))
      (node (ref "R17") (pin "2") (pinfunction "2_2") (pintype "passive"))
      (node (ref "R18") (pin "1") (pinfunction "1_1") (pintype "passive"))
      (node (ref "R18") (pin "2") (pinfunction "2_2") (pintype "passive"))
      (node (ref "R19") (pin "1") (pinfunction "1_1") (pintype "passive"))
      (node (ref "R19") (pin "2") (pinfunction "2_2") (pintype "passive"))
      (node (ref "R22") (pin "1") (pinfunction "1_1") (pintype "passive"))
      (node (ref "R25") (pin "1") (pinfunction "1_1") (pintype "passive"))
      (node (ref "R25") (pin "2") (pinfunction "2_2") (pintype "passive"))
      (node (ref "R5") (pin "1") (pinfunction "1_1") (pintype "passive"))
      (node (ref "R8") (pin "2") (pinfunction "2_2") (pintype "passive"))
      (node (ref "RADIO_IN") (pin "10") (pinfunction "10_10") (pintype "passive"))
      (node (ref "SONAR") (pin "4") (pinfunction "S_4") (pintype "passive"))
      (node (ref "SPI") (pin "1") (pinfunction "1_1") (pintype "passive"))
      (node (ref "SV3") (pin "8") (pinfunction "8_8") (pintype "passive"))
      (node (ref "SV4") (pin "1") (pinfunction "1_1") (pintype "passive"))
      (node (ref "SV4") (pin "2") (pinfunction "2_2") (pintype "passive"))
      (node (ref "SV5") (pin "1") (pinfunction "1_1") (pintype "passive"))
      (node (ref "SV5") (pin "2") (pinfunction "2_2") (pintype "passive"))
      (node (ref "TELEMETRY") (pin "1") (pinfunction "S_1") (pintype "passive"))
      (node (ref "UART_GPS") (pin "2") (pinfunction "2_2") (pintype "passive"))
      (node (ref "USB") (pin "5") (pinfunction "5_5") (pintype "passive"))
      (node (ref "ZQ1") (pin "2") (pinfunction "2_2") (pintype "bidirectional"))
    )
    (net (code "55") (name "Net-(BATERY-Pad2)") (class "Default")
      (node (ref "BATERY") (pin "2") (pinfunction "2_2") (pintype "passive"))
      (node (ref "R21") (pin "1") (pinfunction "1_1") (pintype "passive"))
    )
    (net (code "56") (name "Net-(D1-A1)") (class "Default")
      (node (ref "D1") (pin "1") (pinfunction "A1_1") (pintype "passive"))
      (node (ref "D1") (pin "2") (pinfunction "A2_2") (pintype "passive"))
      (node (ref "M1") (pin "2") (pinfunction "2_2") (pintype "passive"))
      (node (ref "M2") (pin "2") (pinfunction "2_2") (pintype "passive"))
      (node (ref "M3") (pin "2") (pinfunction "2_2") (pintype "passive"))
      (node (ref "M4") (pin "2") (pinfunction "2_2") (pintype "passive"))
      (node (ref "M5") (pin "2") (pinfunction "2_2") (pintype "passive"))
      (node (ref "M6") (pin "2") (pinfunction "2_2") (pintype "passive"))
      (node (ref "M7") (pin "2") (pinfunction "2_2") (pintype "passive"))
      (node (ref "M8") (pin "2") (pinfunction "2_2") (pintype "passive"))
      (node (ref "SV4") (pin "3") (pinfunction "3_3") (pintype "passive"))
      (node (ref "SV4") (pin "4") (pinfunction "4_4") (pintype "passive"))
      (node (ref "SV5") (pin "3") (pinfunction "3_3") (pintype "passive"))
      (node (ref "SV5") (pin "4") (pinfunction "4_4") (pintype "passive"))
    )
    (net (code "57") (name "Net-(D3-A1)") (class "Default")
      (node (ref "D3") (pin "1") (pinfunction "A1_1") (pintype "passive"))
      (node (ref "D3") (pin "2") (pinfunction "A2_2") (pintype "passive"))
      (node (ref "R4") (pin "1") (pinfunction "1_1") (pintype "passive"))
      (node (ref "USB") (pin "1") (pinfunction "1_1") (pintype "passive"))
    )
    (net (code "58") (name "Net-(DA1-CBYD)") (class "Default")
      (node (ref "C5") (pin "1") (pinfunction "1_1") (pintype "passive"))
      (node (ref "DA1") (pin "4") (pinfunction "CBYD_4") (pintype "bidirectional"))
    )
    (net (code "59") (name "Net-(DA2-CBYD)") (class "Default")
      (node (ref "C1") (pin "1") (pinfunction "1_1") (pintype "passive"))
      (node (ref "DA2") (pin "4") (pinfunction "CBYD_4") (pintype "bidirectional"))
    )
    (net (code "60") (name "Net-(DA2-ON_0F)") (class "Default")
      (node (ref "C7") (pin "1") (pinfunction "1_1") (pintype "passive"))
      (node (ref "DA2") (pin "1") (pinfunction "VIN_1") (pintype "bidirectional"))
      (node (ref "DA2") (pin "3") (pinfunction "ON_0F_3") (pintype "bidirectional"))
      (node (ref "R16") (pin "1") (pinfunction "1_1") (pintype "passive"))
    )
    (net (code "61") (name "Net-(DA2-OUT)") (class "Default")
      (node (ref "C2") (pin "1") (pinfunction "1_1") (pintype "passive"))
      (node (ref "C3") (pin "+") (pinfunction "+_+") (pintype "passive"))
      (node (ref "C6") (pin "1") (pinfunction "1_1") (pintype "passive"))
      (node (ref "DA2") (pin "5") (pinfunction "OUT_5") (pintype "bidirectional"))
      (node (ref "R24") (pin "1") (pinfunction "1_1") (pintype "passive"))
      (node (ref "R6") (pin "1") (pinfunction "1_1") (pintype "passive"))
    )
    (net (code "62") (name "Net-(DD1-BOOT0)") (class "Default")
      (node (ref "BOOT0") (pin "1") (pinfunction "1_1") (pintype "passive"))
      (node (ref "DD1") (pin "94") (pinfunction "BOOT0_94") (pintype "bidirectional"))
      (node (ref "R8") (pin "1") (pinfunction "1_1") (pintype "passive"))
    )
    (net (code "63") (name "Net-(DD1-NC)") (class "Default")
      (node (ref "C26") (pin "1") (pinfunction "1_1") (pintype "passive"))
      (node (ref "DD1") (pin "73") (pinfunction "NC_73") (pintype "bidirectional"))
    )
    (net (code "64") (name "Net-(DD1-NRST)") (class "Default")
      (node (ref "C25") (pin "1") (pinfunction "1_1") (pintype "passive"))
      (node (ref "DD1") (pin "14") (pinfunction "NRST_14") (pintype "bidirectional"))
      (node (ref "R9") (pin "2") (pinfunction "2_2") (pintype "passive"))
    )
    (net (code "65") (name "Net-(DD1-OSCIN)") (class "Default")
      (node (ref "DD1") (pin "12") (pinfunction "OSCIN_12") (pintype "bidirectional"))
      (node (ref "R15") (pin "1") (pinfunction "1_1") (pintype "passive"))
    )
    (net (code "66") (name "Net-(DD1-OSCOUT)") (class "Default")
      (node (ref "DD1") (pin "13") (pinfunction "OSCOUT_13") (pintype "bidirectional"))
      (node (ref "ZQ1") (pin "1") (pinfunction "1_1") (pintype "bidirectional"))
    )
    (net (code "67") (name "Net-(DD1-PA11)") (class "Default")
      (node (ref "DD1") (pin "70") (pinfunction "PA11_70") (pintype "bidirectional"))
      (node (ref "R1") (pin "1") (pinfunction "1_1") (pintype "passive"))
    )
    (net (code "68") (name "Net-(DD1-PA12)") (class "Default")
      (node (ref "DD1") (pin "71") (pinfunction "PA12_71") (pintype "bidirectional"))
      (node (ref "R2") (pin "1") (pinfunction "1_1") (pintype "passive"))
      (node (ref "R3") (pin "2") (pinfunction "2_2") (pintype "passive"))
    )
    (net (code "69") (name "Net-(DD1-PA13)") (class "Default")
      (node (ref "DD1") (pin "72") (pinfunction "PA13_72") (pintype "bidirectional"))
      (node (ref "SWDIO") (pin "TP") (pinfunction "TP_TP") (pintype "input"))
    )
    (net (code "70") (name "Net-(DD1-PA14)") (class "Default")
      (node (ref "DD1") (pin "76") (pinfunction "PA14_76") (pintype "bidirectional"))
      (node (ref "SWCLK") (pin "TP") (pinfunction "TP_TP") (pintype "input"))
    )
    (net (code "71") (name "Net-(DD1-PD4)") (class "Default")
      (node (ref "DD1") (pin "85") (pinfunction "PD4_85") (pintype "bidirectional"))
      (node (ref "R4") (pin "2") (pinfunction "2_2") (pintype "passive"))
      (node (ref "R5") (pin "2") (pinfunction "2_2") (pintype "passive"))
    )
    (net (code "72") (name "Net-(DD1-PD11)") (class "Default")
      (node (ref "DD1") (pin "58") (pinfunction "PD11_58") (pintype "bidirectional"))
      (node (ref "R23") (pin "2") (pinfunction "2_2") (pintype "passive"))
    )
    (net (code "73") (name "Net-(DD1-PE0)") (class "Default")
      (node (ref "DD1") (pin "97") (pinfunction "PE0_97") (pintype "bidirectional"))
      (node (ref "RN3") (pin "5") (pinfunction "2_5") (pintype "passive"))
    )
    (net (code "74") (name "Net-(DD1-PE1)") (class "Default")
      (node (ref "DD1") (pin "98") (pinfunction "PE1_98") (pintype "bidirectional"))
      (node (ref "RN3") (pin "6") (pinfunction "2_6") (pintype "passive"))
    )
    (net (code "75") (name "Net-(DD1-PE2)") (class "Default")
      (node (ref "DD1") (pin "1") (pinfunction "PE2_1") (pintype "bidirectional"))
      (node (ref "RN3") (pin "7") (pinfunction "2_7") (pintype "passive"))
    )
    (net (code "76") (name "Net-(DD1-PE3)") (class "Default")
      (node (ref "DD1") (pin "2") (pinfunction "PE3_2") (pintype "bidirectional"))
      (node (ref "RN3") (pin "8") (pinfunction "2_8") (pintype "passive"))
    )
    (net (code "77") (name "Net-(DD1-VSS2)") (class "Default")
      (node (ref "C4") (pin "1") (pinfunction "1_1") (pintype "passive"))
      (node (ref "DD1") (pin "49") (pinfunction "VSS2_49") (pintype "bidirectional"))
    )
    (net (code "78") (name "Net-(DD2-C1)") (class "Default")
      (node (ref "C10") (pin "1") (pinfunction "1_1") (pintype "passive"))
      (node (ref "DD2") (pin "10") (pinfunction "C1_10") (pintype "bidirectional"))
    )
    (net (code "79") (name "Net-(DD2-STEP_C)") (class "Default")
      (node (ref "C11") (pin "2") (pinfunction "2_2") (pintype "passive"))
      (node (ref "DD2") (pin "12") (pinfunction "STEP_C_12") (pintype "bidirectional"))
    )
    (net (code "80") (name "Net-(DD2-STEP_P)") (class "Default")
      (node (ref "C11") (pin "1") (pinfunction "1_1") (pintype "passive"))
      (node (ref "DD2") (pin "8") (pinfunction "STEP_P_8") (pintype "bidirectional"))
    )
    (net (code "81") (name "Net-(DD4-CPUOT)") (class "Default")
      (node (ref "C16") (pin "1") (pinfunction "1_1") (pintype "passive"))
      (node (ref "DD4") (pin "20") (pinfunction "CPUOT_20") (pintype "bidirectional"))
    )
    (net (code "82") (name "Net-(DD4-REGOUT)") (class "Default")
      (node (ref "C17") (pin "1") (pinfunction "1_1") (pintype "passive"))
      (node (ref "DD4") (pin "10") (pinfunction "REGOUT_10") (pintype "bidirectional"))
    )
    (net (code "83") (name "Net-(LED1-6-PadA)") (class "Default")
      (node (ref "LED1-6") (pin "A") (pinfunction "A_A") (pintype "passive"))
      (node (ref "RN3") (pin "1") (pinfunction "1_1") (pintype "passive"))
    )
    (net (code "84") (name "Net-(LED1-PadA)") (class "Default")
      (node (ref "LED1") (pin "A") (pinfunction "A_A") (pintype "passive"))
      (node (ref "R20") (pin "2") (pinfunction "2_2") (pintype "passive"))
    )
    (net (code "85") (name "Net-(LED3-PadA)") (class "Default")
      (node (ref "LED3") (pin "A") (pinfunction "A_A") (pintype "passive"))
      (node (ref "R6") (pin "2") (pinfunction "2_2") (pintype "passive"))
    )
    (net (code "86") (name "Net-(R1-Pad2)") (class "Default")
      (node (ref "R1") (pin "2") (pinfunction "2_2") (pintype "passive"))
      (node (ref "USB") (pin "2") (pinfunction "2_2") (pintype "passive"))
    )
    (net (code "87") (name "Net-(R2-Pad2)") (class "Default")
      (node (ref "R2") (pin "2") (pinfunction "2_2") (pintype "passive"))
      (node (ref "USB") (pin "3") (pinfunction "3_3") (pintype "passive"))
    )
    (net (code "88") (name "Net-(R15-Pad2)") (class "Default")
      (node (ref "R15") (pin "2") (pinfunction "2_2") (pintype "passive"))
      (node (ref "ZQ1") (pin "3") (pinfunction "3_3") (pintype "bidirectional"))
    )
    (net (code "89") (name "Net-(RADIO_IN-Pad2)") (class "Default")
      (node (ref "RADIO_IN") (pin "2") (pinfunction "2_2") (pintype "passive"))
      (node (ref "RN2") (pin "1") (pinfunction "1_1") (pintype "passive"))
    )
    (net (code "90") (name "Net-(RADIO_IN-Pad5)") (class "Default")
      (node (ref "RADIO_IN") (pin "5") (pinfunction "5_5") (pintype "passive"))
      (node (ref "RN1") (pin "1") (pinfunction "1_1") (pintype "passive"))
    )
    (net (code "91") (name "Net-(RN1B-1)") (class "Default")
      (node (ref "RADIO_IN") (pin "6") (pinfunction "6_6") (pintype "passive"))
      (node (ref "RN1") (pin "2") (pinfunction "1_2") (pintype "passive"))
    )
    (net (code "92") (name "Net-(RN1C-1)") (class "Default")
      (node (ref "RADIO_IN") (pin "7") (pinfunction "7_7") (pintype "passive"))
      (node (ref "RN1") (pin "3") (pinfunction "1_3") (pintype "passive"))
    )
    (net (code "93") (name "Net-(RN1D-1)") (class "Default")
      (node (ref "RADIO_IN") (pin "9") (pinfunction "9_9") (pintype "passive"))
      (node (ref "RN1") (pin "4") (pinfunction "1_4") (pintype "passive"))
    )
    (net (code "94") (name "Net-(RN2B-1)") (class "Default")
      (node (ref "RADIO_IN") (pin "1") (pinfunction "1_1") (pintype "passive"))
      (node (ref "RN2") (pin "2") (pinfunction "1_2") (pintype "passive"))
    )
    (net (code "95") (name "Net-(RN2C-1)") (class "Default")
      (node (ref "RADIO_IN") (pin "4") (pinfunction "4_4") (pintype "passive"))
      (node (ref "RN2") (pin "3") (pinfunction "1_3") (pintype "passive"))
    )
    (net (code "96") (name "Net-(RN2D-1)") (class "Default")
      (node (ref "RADIO_IN") (pin "3") (pinfunction "3_3") (pintype "passive"))
      (node (ref "RN2") (pin "4") (pinfunction "1_4") (pintype "passive"))
    )
    (net (code "97") (name "Net-(RN3B-1)") (class "Default")
      (node (ref "LED5") (pin "A") (pinfunction "A_A") (pintype "passive"))
      (node (ref "RN3") (pin "2") (pinfunction "1_2") (pintype "passive"))
    )
    (net (code "98") (name "Net-(RN3C-1)") (class "Default")
      (node (ref "LED4") (pin "A") (pinfunction "A_A") (pintype "passive"))
      (node (ref "RN3") (pin "3") (pinfunction "1_3") (pintype "passive"))
    )
    (net (code "99") (name "Net-(RN3D-1)") (class "Default")
      (node (ref "LED2") (pin "A") (pinfunction "A_A") (pintype "passive"))
      (node (ref "RN3") (pin "4") (pinfunction "1_4") (pintype "passive"))
    )
    (net (code "100") (name "V+") (class "Default")
      (node (ref "C14") (pin "1") (pinfunction "1_1") (pintype "passive"))
      (node (ref "C15") (pin "1") (pinfunction "1_1") (pintype "passive"))
      (node (ref "DD1") (pin "21") (pinfunction "VREF+_21") (pintype "bidirectional"))
      (node (ref "DD1") (pin "22") (pinfunction "VDDA_22") (pintype "bidirectional"))
      (node (ref "DD2") (pin "2") (pinfunction "VDD_2") (pintype "bidirectional"))
      (node (ref "DD2") (pin "4") (pinfunction "S1_4") (pintype "bidirectional"))
      (node (ref "DD4") (pin "13") (pinfunction "VDD_13") (pintype "bidirectional"))
      (node (ref "R24") (pin "2") (pinfunction "2_2") (pintype "passive"))
    )
    (net (code "101") (name "VCC") (class "Default")
      (node (ref "BOOT0") (pin "2") (pinfunction "2_2") (pintype "passive"))
      (node (ref "C13") (pin "+") (pinfunction "+_+") (pintype "passive"))
      (node (ref "C18") (pin "1") (pinfunction "1_1") (pintype "passive"))
      (node (ref "C19") (pin "1") (pinfunction "1_1") (pintype "passive"))
      (node (ref "C8") (pin "1") (pinfunction "1_1") (pintype "passive"))
      (node (ref "C9") (pin "1") (pinfunction "1_1") (pintype "passive"))
      (node (ref "DA1") (pin "5") (pinfunction "OUT_5") (pintype "bidirectional"))
      (node (ref "DD1") (pin "100") (pinfunction "VDD3_100") (pintype "bidirectional"))
      (node (ref "DD1") (pin "11") (pinfunction "VDD5_11") (pintype "bidirectional"))
      (node (ref "DD1") (pin "19") (pinfunction "VSSA_19") (pintype "bidirectional"))
      (node (ref "DD1") (pin "28") (pinfunction "VDD4_28") (pintype "bidirectional"))
      (node (ref "DD1") (pin "50") (pinfunction "VDD1_50") (pintype "bidirectional"))
      (node (ref "DD1") (pin "6") (pinfunction "VBAT_6") (pintype "bidirectional"))
      (node (ref "DD1") (pin "75") (pinfunction "VDD2_75") (pintype "bidirectional"))
      (node (ref "DD2") (pin "13") (pinfunction "VDD_IO_13") (pintype "bidirectional"))
      (node (ref "DD3") (pin "7") (pinfunction "VCC_7") (pintype "bidirectional"))
      (node (ref "DD3") (pin "8") (pinfunction "WC_8") (pintype "bidirectional"))
      (node (ref "DD5") (pin "1") (pinfunction "VDD_1") (pintype "bidirectional"))
      (node (ref "DD5") (pin "2") (pinfunction "PS_2") (pintype "bidirectional"))
      (node (ref "DD6") (pin "3") (pinfunction "WP_3") (pintype "bidirectional"))
      (node (ref "DD6") (pin "7") (pinfunction "HOLD_7") (pintype "bidirectional"))
      (node (ref "DD6") (pin "8") (pinfunction "VCC_8") (pintype "bidirectional"))
      (node (ref "R10") (pin "1") (pinfunction "1_1") (pintype "passive"))
      (node (ref "R12") (pin "1") (pinfunction "1_1") (pintype "passive"))
      (node (ref "R14") (pin "2") (pinfunction "2_2") (pintype "passive"))
      (node (ref "R20") (pin "1") (pinfunction "1_1") (pintype "passive"))
      (node (ref "R3") (pin "1") (pinfunction "1_1") (pintype "passive"))
      (node (ref "R7") (pin "2") (pinfunction "2_2") (pintype "passive"))
      (node (ref "R9") (pin "1") (pinfunction "1_1") (pintype "passive"))
    )
    (net (code "102") (name "unconnected-(DD1-PA8-Pad67)") (class "Default")
      (node (ref "DD1") (pin "67") (pinfunction "PA8_67") (pintype "bidirectional"))
    )
    (net (code "103") (name "unconnected-(DD1-PC5-Pad34)") (class "Default")
      (node (ref "DD1") (pin "34") (pinfunction "PC5_34") (pintype "bidirectional"))
    )
    (net (code "104") (name "unconnected-(DD1-PC10-Pad78)") (class "Default")
      (node (ref "DD1") (pin "78") (pinfunction "PC10_78") (pintype "bidirectional"))
    )
    (net (code "105") (name "unconnected-(DD1-PC11-Pad79)") (class "Default")
      (node (ref "DD1") (pin "79") (pinfunction "PC11_79") (pintype "bidirectional"))
    )
    (net (code "106") (name "unconnected-(DD1-PC12-Pad80)") (class "Default")
      (node (ref "DD1") (pin "80") (pinfunction "PC12_80") (pintype "bidirectional"))
    )
    (net (code "107") (name "unconnected-(DD1-PC13-Pad7)") (class "Default")
      (node (ref "DD1") (pin "7") (pinfunction "PC13_7") (pintype "bidirectional"))
    )
    (net (code "108") (name "unconnected-(DD1-PD0-Pad81)") (class "Default")
      (node (ref "DD1") (pin "81") (pinfunction "PD0_81") (pintype "bidirectional"))
    )
    (net (code "109") (name "unconnected-(DD1-PD1-Pad82)") (class "Default")
      (node (ref "DD1") (pin "82") (pinfunction "PD1_82") (pintype "bidirectional"))
    )
    (net (code "110") (name "unconnected-(DD1-PD2-Pad83)") (class "Default")
      (node (ref "DD1") (pin "83") (pinfunction "PD2_83") (pintype "bidirectional"))
    )
    (net (code "111") (name "unconnected-(DD1-PD3-Pad84)") (class "Default")
      (node (ref "DD1") (pin "84") (pinfunction "PD3_84") (pintype "bidirectional"))
    )
    (net (code "112") (name "unconnected-(DD1-PD7-Pad88)") (class "Default")
      (node (ref "DD1") (pin "88") (pinfunction "PD7_88") (pintype "bidirectional"))
    )
    (net (code "113") (name "unconnected-(DD1-PD12-Pad59)") (class "Default")
      (node (ref "DD1") (pin "59") (pinfunction "PD12_59") (pintype "bidirectional"))
    )
    (net (code "114") (name "unconnected-(DD1-PE4-Pad3)") (class "Default")
      (node (ref "DD1") (pin "3") (pinfunction "PE4_3") (pintype "bidirectional"))
    )
    (net (code "115") (name "unconnected-(DD1-PE7-Pad38)") (class "Default")
      (node (ref "DD1") (pin "38") (pinfunction "PE7_38") (pintype "bidirectional"))
    )
    (net (code "116") (name "unconnected-(DD1-PE8-Pad39)") (class "Default")
      (node (ref "DD1") (pin "39") (pinfunction "PE8_39") (pintype "bidirectional"))
    )
    (net (code "117") (name "unconnected-(DD1-PE10-Pad41)") (class "Default")
      (node (ref "DD1") (pin "41") (pinfunction "PE10_41") (pintype "bidirectional"))
    )
    (net (code "118") (name "unconnected-(DD1-PE12-Pad43)") (class "Default")
      (node (ref "DD1") (pin "43") (pinfunction "PE12_43") (pintype "bidirectional"))
    )
    (net (code "119") (name "unconnected-(DD1-PE15-Pad46)") (class "Default")
      (node (ref "DD1") (pin "46") (pinfunction "PE15_46") (pintype "bidirectional"))
    )
    (net (code "120") (name "unconnected-(DD2-NC1-Pad3)") (class "Default")
      (node (ref "DD2") (pin "3") (pinfunction "NC1_3") (pintype "bidirectional"))
    )
    (net (code "121") (name "unconnected-(DD2-NC2-Pad5)") (class "Default")
      (node (ref "DD2") (pin "5") (pinfunction "NC2_5") (pintype "bidirectional"))
    )
    (net (code "122") (name "unconnected-(DD2-NC3-Pad6)") (class "Default")
      (node (ref "DD2") (pin "6") (pinfunction "NC3_6") (pintype "bidirectional"))
    )
    (net (code "123") (name "unconnected-(DD2-NC4-Pad7)") (class "Default")
      (node (ref "DD2") (pin "7") (pinfunction "NC4_7") (pintype "bidirectional"))
    )
    (net (code "124") (name "unconnected-(DD2-NC5-Pad14)") (class "Default")
      (node (ref "DD2") (pin "14") (pinfunction "NC5_14") (pintype "bidirectional"))
    )
    (net (code "125") (name "unconnected-(DD4-AUXCL-Pad7)") (class "Default")
      (node (ref "DD4") (pin "7") (pinfunction "AUXCL_7") (pintype "bidirectional"))
    )
    (net (code "126") (name "unconnected-(DD4-AUXDA-Pad6)") (class "Default")
      (node (ref "DD4") (pin "6") (pinfunction "AUXDA_6") (pintype "bidirectional"))
    )
    (net (code "127") (name "unconnected-(DD4-CLKOUT-Pad22)") (class "Default")
      (node (ref "DD4") (pin "22") (pinfunction "CLKOUT_22") (pintype "bidirectional"))
    )
    (net (code "128") (name "unconnected-(DD4-NC1-Pad2)") (class "Default")
      (node (ref "DD4") (pin "2") (pinfunction "NC1_2") (pintype "bidirectional"))
    )
    (net (code "129") (name "unconnected-(DD4-NC3-Pad4)") (class "Default")
      (node (ref "DD4") (pin "4") (pinfunction "NC3_4") (pintype "bidirectional"))
    )
    (net (code "130") (name "unconnected-(DD4-NC4-Pad5)") (class "Default")
      (node (ref "DD4") (pin "5") (pinfunction "NC4_5") (pintype "bidirectional"))
    )
    (net (code "131") (name "unconnected-(DD4-NC5-Pad14)") (class "Default")
      (node (ref "DD4") (pin "14") (pinfunction "NC5_14") (pintype "bidirectional"))
    )
    (net (code "132") (name "unconnected-(DD4-NC6-Pad15)") (class "Default")
      (node (ref "DD4") (pin "15") (pinfunction "NC6_15") (pintype "bidirectional"))
    )
    (net (code "133") (name "unconnected-(DD4-NC7-Pad16)") (class "Default")
      (node (ref "DD4") (pin "16") (pinfunction "NC7_16") (pintype "bidirectional"))
    )
    (net (code "134") (name "unconnected-(DD4-NC8-Pad17)") (class "Default")
      (node (ref "DD4") (pin "17") (pinfunction "NC8_17") (pintype "bidirectional"))
    )
    (net (code "135") (name "unconnected-(DD4-NS2-Pad3)") (class "Default")
      (node (ref "DD4") (pin "3") (pinfunction "NS2_3") (pintype "bidirectional"))
    )
    (net (code "136") (name "unconnected-(DD4-RESV1-Pad21)") (class "Default")
      (node (ref "DD4") (pin "21") (pinfunction "RESV1_21") (pintype "bidirectional"))
    )
    (net (code "137") (name "unconnected-(DD4-RESV2-Pad19)") (class "Default")
      (node (ref "DD4") (pin "19") (pinfunction "RESV2_19") (pintype "bidirectional"))
    )
    (net (code "138") (name "unconnected-(DD5-MISO-Pad6)") (class "Default")
      (node (ref "DD5") (pin "6") (pinfunction "MISO_6") (pintype "bidirectional"))
    )
    (net (code "139") (name "unconnected-(USB-Pad4)") (class "Default")
      (node (ref "USB") (pin "4") (pinfunction "4_4") (pintype "passive"))
    )
  )
)
